# BorneChargement.net
KiCad netlist of a schematic drawn in Altium Designer
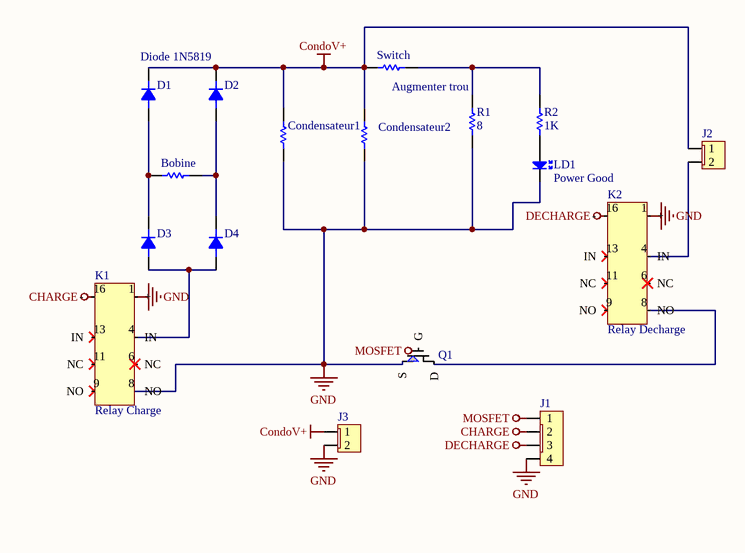
[diagram p0: BorneChargement.SchDoc]

(export (version "E")
  (design (tool "Eeschema 10.0.6"))
  (components
    (comp (ref "Bobine")
      (value "Res 1/4W")
      (footprint "Axial 0.4\" Step")
      (description "Resistor")
      (fields (field (name "PUBLISHER") "Altium Limited"))
      (libsource (lib "Lib Sch") (part "Res 1/4W"))
    )
    (comp (ref "Condensateur1")
      (value "Res 1/4W")
      (footprint "Axial 0.4\" Step")
      (description "Resistor")
      (fields (field (name "PUBLISHER") "Altium Limited"))
      (libsource (lib "Lib Sch") (part "Res 1/4W"))
    )
    (comp (ref "Condensateur2")
      (value "Res 1/4W")
      (footprint "Axial 0.4\" Step")
      (description "Resistor")
      (fields (field (name "PUBLISHER") "Altium Limited"))
      (libsource (lib "Lib Sch") (part "Res 1/4W"))
    )
    (comp (ref "D1")
      (value "Diode 1N5819")
      (footprint "DO-41")
      (description "Diode")
      (fields (field (name "PUBLISHER") "Altium Limited"))
      (libsource (lib "Lib Sch") (part "Diode 1N4004"))
    )
    (comp (ref "D2")
      (value "Diode 1N4004")
      (footprint "DO-41")
      (description "Diode")
      (fields (field (name "PUBLISHER") "Altium Limited"))
      (libsource (lib "Lib Sch") (part "Diode 1N4004"))
    )
    (comp (ref "D3")
      (value "Diode 1N4004")
      (footprint "DO-41")
      (description "Diode")
      (fields (field (name "PUBLISHER") "Altium Limited"))
      (libsource (lib "Lib Sch") (part "Diode 1N4004"))
    )
    (comp (ref "D4")
      (value "Diode 1N4004")
      (footprint "DO-41")
      (description "Diode")
      (fields (field (name "PUBLISHER") "Altium Limited"))
      (libsource (lib "Lib Sch") (part "Diode 1N4004"))
    )
    (comp (ref "J1")
      (value "MTA100-4")
      (footprint "MTA100-4 MF")
      (description "MTA100-4M")
      (libsource (lib "Lib Sch") (part "MTA100-4"))
    )
    (comp (ref "J2")
      (value "Input")
      (footprint "MTA100-2")
      (description "MTA Male 0 Degres")
      (libsource (lib "Lib Sch") (part "MTA100-2"))
    )
    (comp (ref "J3")
      (value "Input")
      (footprint "MTA100-2")
      (description "MTA Male 0 Degres")
      (libsource (lib "Lib Sch") (part "MTA100-2"))
    )
    (comp (ref "K1")
      (value "Relay Charge")
      (footprint "PCBComponent_1")
      (libsource (lib "Relay") (part "Component_1"))
    )
    (comp (ref "K2")
      (value "Relay Decharge")
      (footprint "PCBComponent_1")
      (libsource (lib "Relay") (part "Component_1"))
    )
    (comp (ref "LD1")
      (value "Power Good")
      (footprint "LED 3mm Vertical")
      (description "Through Hole")
      (fields (field (name "PUBLISHER") "Altium Limited"))
      (libsource (lib "Lib Sch") (part "LED 3mm Vertical"))
    )
    (comp (ref "Q1")
      (value "Component_1")
      (footprint "Transistor:PCBComponent_1")
      (libsource (lib "Transistor") (part "Component_1"))
    )
    (comp (ref "R1")
      (value "8")
      (footprint "Axial 0.4\" Step")
      (description "Resistor")
      (fields (field (name "Comment") "Res 1/4W") (field (name "PUBLISHER") "Altium Limited"))
      (libsource (lib "Lib Sch") (part "Res 1/4W"))
    )
    (comp (ref "R2")
      (value "1K")
      (footprint "Axial 0.4\" Step")
      (description "Resistor")
      (fields (field (name "Comment") "Res 1/4W") (field (name "PUBLISHER") "Altium Limited"))
      (libsource (lib "Lib Sch") (part "Res 1/4W"))
    )
    (comp (ref "Switch")
      (value "Res 1/4W")
      (footprint "Axial 0.4\" Step")
      (description "Resistor")
      (fields (field (name "PUBLISHER") "Altium Limited"))
      (libsource (lib "Lib Sch") (part "Res 1/4W"))
    )
  )
  (nets
    (net (code "1") (name "CHARGE") (class "Default")
      (node (ref "J1") (pin "2") (pinfunction "2_2") (pintype "passive"))
      (node (ref "K1") (pin "16") (pinfunction "-_16") (pintype "passive"))
    )
    (net (code "2") (name "CondoV+") (class "Default")
      (node (ref "Condensateur1") (pin "1") (pinfunction "1_1") (pintype "passive"))
      (node (ref "Condensateur2") (pin "1") (pinfunction "1_1") (pintype "passive"))
      (node (ref "D1") (pin "1") (pinfunction "1_1") (pintype "passive"))
      (node (ref "D2") (pin "1") (pinfunction "1_1") (pintype "passive"))
      (node (ref "J2") (pin "1") (pinfunction "1_1") (pintype "passive"))
      (node (ref "J3") (pin "1") (pinfunction "1_1") (pintype "passive"))
      (node (ref "Switch") (pin "1") (pinfunction "1_1") (pintype "passive"))
    )
    (net (code "3") (name "DECHARGE") (class "Default")
      (node (ref "J1") (pin "3") (pinfunction "3_3") (pintype "passive"))
      (node (ref "K2") (pin "16") (pinfunction "-_16") (pintype "passive"))
    )
    (net (code "4") (name "GND") (class "Default")
      (node (ref "Condensateur1") (pin "2") (pinfunction "2_2") (pintype "passive"))
      (node (ref "Condensateur2") (pin "2") (pinfunction "2_2") (pintype "passive"))
      (node (ref "J1") (pin "4") (pinfunction "4_4") (pintype "passive"))
      (node (ref "J3") (pin "2") (pinfunction "2_2") (pintype "passive"))
      (node (ref "K1") (pin "1") (pinfunction "+_1") (pintype "passive"))
      (node (ref "K1") (pin "8") (pinfunction "NO_8") (pintype "passive"))
      (node (ref "K2") (pin "1") (pinfunction "+_1") (pintype "passive"))
      (node (ref "LD1") (pin "2") (pinfunction "K_2") (pintype "passive"))
      (node (ref "Q1") (pin "S") (pinfunction "S_S") (pintype "passive"))
      (node (ref "R1") (pin "1") (pinfunction "1_1") (pintype "passive"))
    )
    (net (code "5") (name "MOSFET") (class "Default")
      (node (ref "J1") (pin "1") (pinfunction "1_1") (pintype "passive"))
      (node (ref "Q1") (pin "G") (pinfunction "G_G") (pintype "passive"))
    )
    (net (code "6") (name "Net-(Bobine-Pad1)") (class "Default")
      (node (ref "Bobine") (pin "1") (pinfunction "1_1") (pintype "passive"))
      (node (ref "D2") (pin "2") (pinfunction "2_2") (pintype "passive"))
      (node (ref "D4") (pin "1") (pinfunction "1_1") (pintype "passive"))
    )
    (net (code "7") (name "Net-(Bobine-Pad2)") (class "Default")
      (node (ref "Bobine") (pin "2") (pinfunction "2_2") (pintype "passive"))
      (node (ref "D1") (pin "2") (pinfunction "2_2") (pintype "passive"))
      (node (ref "D3") (pin "1") (pinfunction "1_1") (pintype "passive"))
    )
    (net (code "8") (name "Net-(D3-Pad2)") (class "Default")
      (node (ref "D3") (pin "2") (pinfunction "2_2") (pintype "passive"))
      (node (ref "D4") (pin "2") (pinfunction "2_2") (pintype "passive"))
      (node (ref "K1") (pin "4") (pinfunction "IN_4") (pintype "passive"))
    )
    (net (code "9") (name "Net-(J2-Pad2)") (class "Default")
      (node (ref "J2") (pin "2") (pinfunction "2_2") (pintype "passive"))
      (node (ref "K2") (pin "4") (pinfunction "IN_4") (pintype "passive"))
    )
    (net (code "10") (name "Net-(K2-NO-Pad8)") (class "Default")
      (node (ref "K2") (pin "8") (pinfunction "NO_8") (pintype "passive"))
      (node (ref "Q1") (pin "D") (pinfunction "D_D") (pintype "passive"))
    )
    (net (code "11") (name "Net-(LD1-A)") (class "Default")
      (node (ref "LD1") (pin "1") (pinfunction "A_1") (pintype "passive"))
      (node (ref "R2") (pin "1") (pinfunction "1_1") (pintype "passive"))
    )
    (net (code "12") (name "Net-(R1-Pad2)") (class "Default")
      (node (ref "R1") (pin "2") (pinfunction "2_2") (pintype "passive"))
      (node (ref "R2") (pin "2") (pinfunction "2_2") (pintype "passive"))
      (node (ref "Switch") (pin "2") (pinfunction "2_2") (pintype "passive"))
    )
    (net (code "13") (name "unconnected-(K1-IN-Pad13)") (class "Default")
      (node (ref "K1") (pin "13") (pinfunction "IN_13") (pintype "passive+no_connect"))
    )
    (net (code "14") (name "unconnected-(K1-NC-Pad6)") (class "Default")
      (node (ref "K1") (pin "6") (pinfunction "NC_6") (pintype "passive+no_connect"))
    )
    (net (code "15") (name "unconnected-(K1-NC-Pad11)") (class "Default")
      (node (ref "K1") (pin "11") (pinfunction "NC_11") (pintype "passive+no_connect"))
    )
    (net (code "16") (name "unconnected-(K1-NO-Pad9)") (class "Default")
      (node (ref "K1") (pin "9") (pinfunction "NO_9") (pintype "passive+no_connect"))
    )
    (net (code "17") (name "unconnected-(K2-IN-Pad13)") (class "Default")
      (node (ref "K2") (pin "13") (pinfunction "IN_13") (pintype "passive+no_connect"))
    )
    (net (code "18") (name "unconnected-(K2-NC-Pad6)") (class "Default")
      (node (ref "K2") (pin "6") (pinfunction "NC_6") (pintype "passive+no_connect"))
    )
    (net (code "19") (name "unconnected-(K2-NC-Pad11)") (class "Default")
      (node (ref "K2") (pin "11") (pinfunction "NC_11") (pintype "passive+no_connect"))
    )
    (net (code "20") (name "unconnected-(K2-NO-Pad9)") (class "Default")
      (node (ref "K2") (pin "9") (pinfunction "NO_9") (pintype "passive+no_connect"))
    )
  )
)
